# 8-TemperatureSensor.net
KiCad netlist of a schematic drawn in Altium Designer
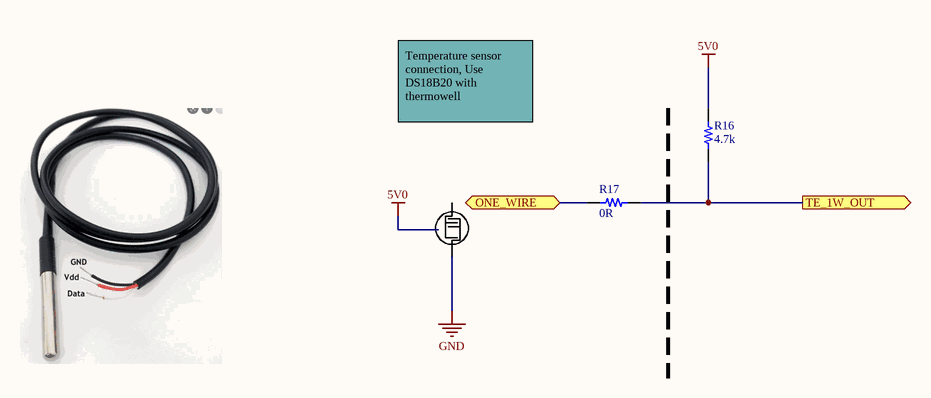
[diagram p0: 8-TemperatureSensor.SchDoc]

(export (version "E")
  (design (tool "Eeschema 10.0.6"))
  (components
    (comp (ref "R16")
      (value "4.7k")
      (footprint "RES 0805_2012")
      (description "RES SMD 1.47K OHM 1% 1/8W 0805")
      (fields (field (name "PART NUMBER") "RC0805FR-071K47L") (field (name "MANUFACTURER") "Yageo"))
      (libsource (lib "Celestial Altium Library - altium_library") (part "Resistor"))
    )
    (comp (ref "R17")
      (value "0R")
      (footprint "RES 0805_2012")
      (description "RES SMD 1.47K OHM 1% 1/8W 0805")
      (fields (field (name "PART NUMBER") "RC0805FR-071K47L") (field (name "MANUFACTURER") "Yageo"))
      (libsource (lib "Celestial Altium Library - altium_library") (part "Resistor"))
    )
  )
  (nets
    (net (code "1") (name "/ONE_WIRE") (class "Default")
      (node (ref "R17") (pin "2") (pinfunction "2_2") (pintype "passive"))
    )
    (net (code "2") (name "/TE_1W_OUT") (class "Default")
      (node (ref "R16") (pin "1") (pinfunction "1_1") (pintype "passive"))
      (node (ref "R17") (pin "1") (pinfunction "1_1") (pintype "passive"))
    )
    (net (code "3") (name "5V0") (class "Default")
      (node (ref "R16") (pin "2") (pinfunction "2_2") (pintype "passive"))
    )
  )
)
